# MyBuffer.net
KiCad netlist of a schematic drawn in EAGLE
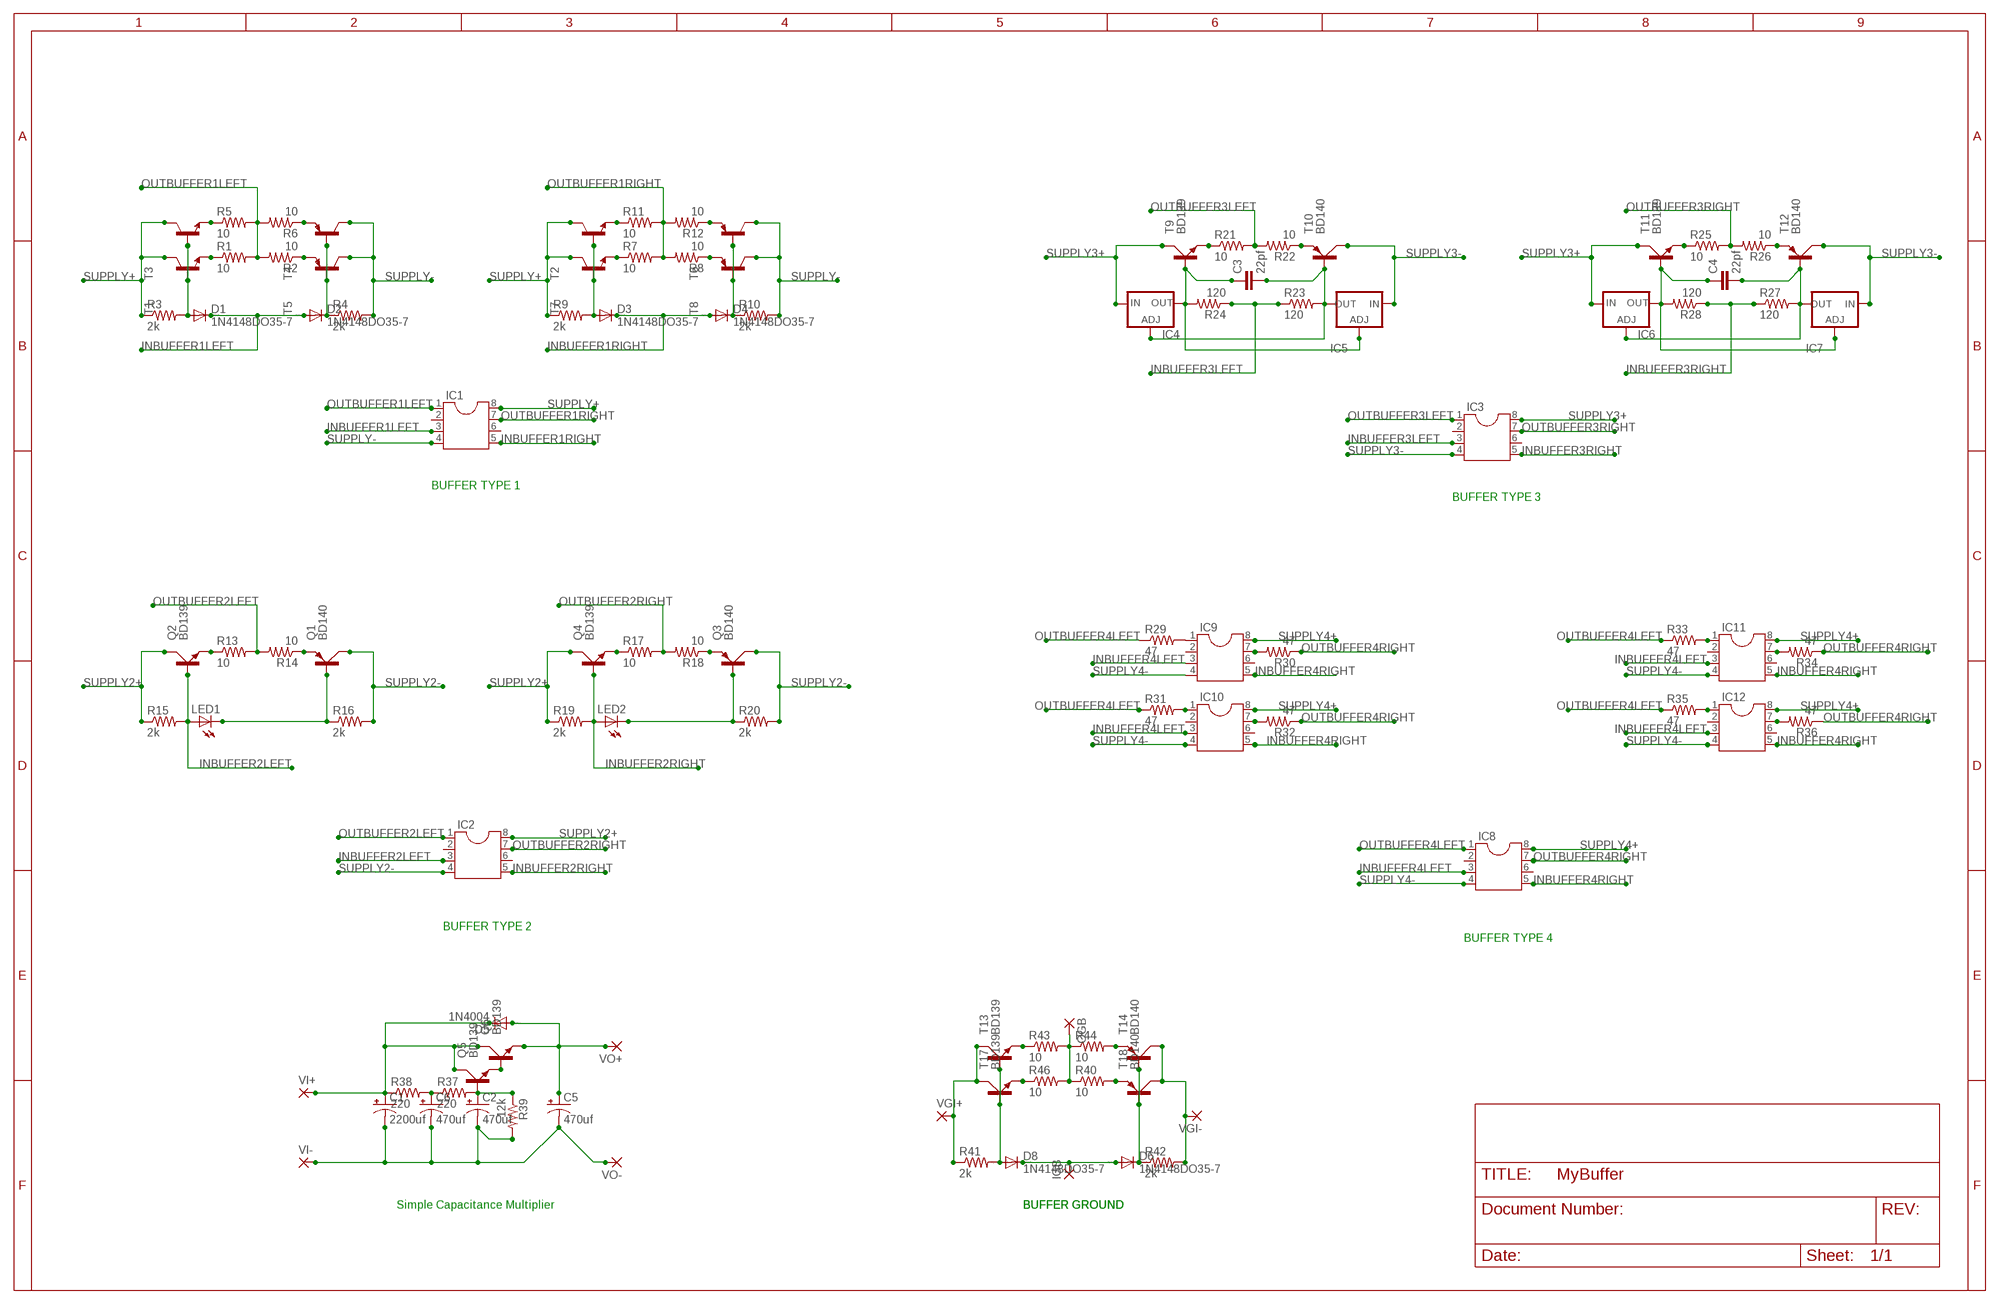
[diagram p0: schematic, sheet 1]

(export (version "E")
  (design (tool "Eeschema 10.0.6"))
  (components
    (comp (ref "C1")
      (value "2200uf")
      (footprint "eagle-import:E7,5-16")
      (libsource (lib "eagle-import") (part "CPOL-USE7.5-16"))
    )
    (comp (ref "C2")
      (value "470uf")
      (footprint "eagle-import:E7,5-16")
      (libsource (lib "eagle-import") (part "CPOL-USE7.5-16"))
    )
    (comp (ref "C3")
      (value "22pf")
      (footprint "eagle-import:C5B2.5")
      (libsource (lib "eagle-import") (part "C5/2.5"))
    )
    (comp (ref "C4")
      (value "22pf")
      (footprint "eagle-import:C5B2.5")
      (libsource (lib "eagle-import") (part "C5/2.5"))
    )
    (comp (ref "C5")
      (value "470uf")
      (footprint "eagle-import:E7,5-16")
      (libsource (lib "eagle-import") (part "CPOL-USE7.5-16"))
    )
    (comp (ref "C6")
      (value "470uf")
      (footprint "eagle-import:E7,5-16")
      (libsource (lib "eagle-import") (part "CPOL-USE7.5-16"))
    )
    (comp (ref "D1")
      (value "1N4148DO35-7")
      (footprint "eagle-import:DO35-7")
      (libsource (lib "eagle-import") (part "1N4148DO35-7"))
    )
    (comp (ref "D2")
      (value "1N4148DO35-7")
      (footprint "eagle-import:DO35-7")
      (libsource (lib "eagle-import") (part "1N4148DO35-7"))
    )
    (comp (ref "D3")
      (value "1N4148DO35-7")
      (footprint "eagle-import:DO35-7")
      (libsource (lib "eagle-import") (part "1N4148DO35-7"))
    )
    (comp (ref "D4")
      (value "1N4148DO35-7")
      (footprint "eagle-import:DO35-7")
      (libsource (lib "eagle-import") (part "1N4148DO35-7"))
    )
    (comp (ref "D5")
      (value "1N4004")
      (footprint "eagle-import:DO41-10")
      (libsource (lib "eagle-import") (part "1N4004"))
    )
    (comp (ref "D6")
      (value "1N4148DO35-7")
      (footprint "eagle-import:DO35-7")
      (libsource (lib "eagle-import") (part "1N4148DO35-7"))
    )
    (comp (ref "D8")
      (value "1N4148DO35-7")
      (footprint "eagle-import:DO35-7")
      (libsource (lib "eagle-import") (part "1N4148DO35-7"))
    )
    (comp (ref "IC1")
      (value "DIL8")
      (footprint "eagle-import:DIL08")
      (libsource (lib "eagle-import") (part "DIL8"))
    )
    (comp (ref "IC2")
      (value "DIL8")
      (footprint "eagle-import:DIL08")
      (libsource (lib "eagle-import") (part "DIL8"))
    )
    (comp (ref "IC3")
      (value "DIL8")
      (footprint "eagle-import:DIL08")
      (libsource (lib "eagle-import") (part "DIL8"))
    )
    (comp (ref "IC4")
      (value "LM317TS")
      (footprint "eagle-import:317TS")
      (libsource (lib "eagle-import") (part "LM317TS"))
    )
    (comp (ref "IC5")
      (value "LM337TS")
      (footprint "eagle-import:337TS")
      (libsource (lib "eagle-import") (part "LM337TS"))
    )
    (comp (ref "IC6")
      (value "LM317TS")
      (footprint "eagle-import:317TS")
      (libsource (lib "eagle-import") (part "LM317TS"))
    )
    (comp (ref "IC7")
      (value "LM337TS")
      (footprint "eagle-import:337TS")
      (libsource (lib "eagle-import") (part "LM337TS"))
    )
    (comp (ref "IC8")
      (value "DIL8")
      (footprint "eagle-import:DIL08")
      (libsource (lib "eagle-import") (part "DIL8"))
    )
    (comp (ref "IC9")
      (value "DIL8")
      (footprint "eagle-import:DIL08")
      (libsource (lib "eagle-import") (part "DIL8"))
    )
    (comp (ref "IC10")
      (value "DIL8")
      (footprint "eagle-import:DIL08")
      (libsource (lib "eagle-import") (part "DIL8"))
    )
    (comp (ref "IC11")
      (value "DIL8")
      (footprint "eagle-import:DIL08")
      (libsource (lib "eagle-import") (part "DIL8"))
    )
    (comp (ref "IC12")
      (value "DIL8")
      (footprint "eagle-import:DIL08")
      (libsource (lib "eagle-import") (part "DIL8"))
    )
    (comp (ref "IGB")
      (value "2,54/0,8")
      (footprint "eagle-import:2,54_0,8")
      (libsource (lib "eagle-import") (part "2,54/0,8"))
    )
    (comp (ref "LED1")
      (value "LED3MM")
      (footprint "eagle-import:LED3MM")
      (libsource (lib "eagle-import") (part "LED3MM"))
    )
    (comp (ref "LED2")
      (value "LED3MM")
      (footprint "eagle-import:LED3MM")
      (libsource (lib "eagle-import") (part "LED3MM"))
    )
    (comp (ref "OGB")
      (value "2,54/0,8")
      (footprint "eagle-import:2,54_0,8")
      (libsource (lib "eagle-import") (part "2,54/0,8"))
    )
    (comp (ref "Q1")
      (value "BD140")
      (footprint "eagle-import:TO126AV")
      (libsource (lib "eagle-import") (part "BD140"))
    )
    (comp (ref "Q2")
      (value "BD139")
      (footprint "eagle-import:TO126AV")
      (libsource (lib "eagle-import") (part "BD139"))
    )
    (comp (ref "Q3")
      (value "BD140")
      (footprint "eagle-import:TO126AV")
      (libsource (lib "eagle-import") (part "BD140"))
    )
    (comp (ref "Q4")
      (value "BD139")
      (footprint "eagle-import:TO126AV")
      (libsource (lib "eagle-import") (part "BD139"))
    )
    (comp (ref "Q5")
      (value "BD139")
      (footprint "eagle-import:TO126AV")
      (libsource (lib "eagle-import") (part "BD139"))
    )
    (comp (ref "Q6")
      (value "BD139")
      (footprint "eagle-import:TO126AV")
      (libsource (lib "eagle-import") (part "BD139"))
    )
    (comp (ref "R1")
      (value "10")
      (footprint "eagle-import:0207_10")
      (libsource (lib "eagle-import") (part "R-US_0207/10"))
    )
    (comp (ref "R2")
      (value "10")
      (footprint "eagle-import:0207_10")
      (libsource (lib "eagle-import") (part "R-US_0207/10"))
    )
    (comp (ref "R3")
      (value "2k")
      (footprint "eagle-import:0207_10")
      (libsource (lib "eagle-import") (part "R-US_0207/10"))
    )
    (comp (ref "R4")
      (value "2k")
      (footprint "eagle-import:0207_10")
      (libsource (lib "eagle-import") (part "R-US_0207/10"))
    )
    (comp (ref "R5")
      (value "10")
      (footprint "eagle-import:0207_2V")
      (libsource (lib "eagle-import") (part "R-US_0207/2V"))
    )
    (comp (ref "R6")
      (value "10")
      (footprint "eagle-import:0207_2V")
      (libsource (lib "eagle-import") (part "R-US_0207/2V"))
    )
    (comp (ref "R7")
      (value "10")
      (footprint "eagle-import:0207_10")
      (libsource (lib "eagle-import") (part "R-US_0207/10"))
    )
    (comp (ref "R8")
      (value "10")
      (footprint "eagle-import:0207_10")
      (libsource (lib "eagle-import") (part "R-US_0207/10"))
    )
    (comp (ref "R9")
      (value "2k")
      (footprint "eagle-import:0207_10")
      (libsource (lib "eagle-import") (part "R-US_0207/10"))
    )
    (comp (ref "R10")
      (value "2k")
      (footprint "eagle-import:0207_10")
      (libsource (lib "eagle-import") (part "R-US_0207/10"))
    )
    (comp (ref "R11")
      (value "10")
      (footprint "eagle-import:0207_2V")
      (libsource (lib "eagle-import") (part "R-US_0207/2V"))
    )
    (comp (ref "R12")
      (value "10")
      (footprint "eagle-import:0207_2V")
      (libsource (lib "eagle-import") (part "R-US_0207/2V"))
    )
    (comp (ref "R13")
      (value "10")
      (footprint "eagle-import:0207_10")
      (libsource (lib "eagle-import") (part "R-US_0207/10"))
    )
    (comp (ref "R14")
      (value "10")
      (footprint "eagle-import:0207_10")
      (libsource (lib "eagle-import") (part "R-US_0207/10"))
    )
    (comp (ref "R15")
      (value "2k")
      (footprint "eagle-import:0207_10")
      (libsource (lib "eagle-import") (part "R-US_0207/10"))
    )
    (comp (ref "R16")
      (value "2k")
      (footprint "eagle-import:0207_10")
      (libsource (lib "eagle-import") (part "R-US_0207/10"))
    )
    (comp (ref "R17")
      (value "10")
      (footprint "eagle-import:0207_10")
      (libsource (lib "eagle-import") (part "R-US_0207/10"))
    )
    (comp (ref "R18")
      (value "10")
      (footprint "eagle-import:0207_10")
      (libsource (lib "eagle-import") (part "R-US_0207/10"))
    )
    (comp (ref "R19")
      (value "2k")
      (footprint "eagle-import:0207_10")
      (libsource (lib "eagle-import") (part "R-US_0207/10"))
    )
    (comp (ref "R20")
      (value "2k")
      (footprint "eagle-import:0207_10")
      (libsource (lib "eagle-import") (part "R-US_0207/10"))
    )
    (comp (ref "R21")
      (value "10")
      (footprint "eagle-import:0207_10")
      (libsource (lib "eagle-import") (part "R-US_0207/10"))
    )
    (comp (ref "R22")
      (value "10")
      (footprint "eagle-import:0207_10")
      (libsource (lib "eagle-import") (part "R-US_0207/10"))
    )
    (comp (ref "R23")
      (value "120")
      (footprint "eagle-import:0207_10")
      (libsource (lib "eagle-import") (part "R-US_0207/10"))
    )
    (comp (ref "R24")
      (value "120")
      (footprint "eagle-import:0207_10")
      (libsource (lib "eagle-import") (part "R-US_0207/10"))
    )
    (comp (ref "R25")
      (value "10")
      (footprint "eagle-import:0207_10")
      (libsource (lib "eagle-import") (part "R-US_0207/10"))
    )
    (comp (ref "R26")
      (value "10")
      (footprint "eagle-import:0207_10")
      (libsource (lib "eagle-import") (part "R-US_0207/10"))
    )
    (comp (ref "R27")
      (value "120")
      (footprint "eagle-import:0207_10")
      (libsource (lib "eagle-import") (part "R-US_0207/10"))
    )
    (comp (ref "R28")
      (value "120")
      (footprint "eagle-import:0207_10")
      (libsource (lib "eagle-import") (part "R-US_0207/10"))
    )
    (comp (ref "R29")
      (value "47")
      (footprint "eagle-import:0207_10")
      (libsource (lib "eagle-import") (part "R-US_0207/10"))
    )
    (comp (ref "R30")
      (value "47")
      (footprint "eagle-import:0207_10")
      (libsource (lib "eagle-import") (part "R-US_0207/10"))
    )
    (comp (ref "R31")
      (value "47")
      (footprint "eagle-import:0207_10")
      (libsource (lib "eagle-import") (part "R-US_0207/10"))
    )
    (comp (ref "R32")
      (value "47")
      (footprint "eagle-import:0207_10")
      (libsource (lib "eagle-import") (part "R-US_0207/10"))
    )
    (comp (ref "R33")
      (value "47")
      (footprint "eagle-import:0207_10")
      (libsource (lib "eagle-import") (part "R-US_0207/10"))
    )
    (comp (ref "R34")
      (value "47")
      (footprint "eagle-import:0207_10")
      (libsource (lib "eagle-import") (part "R-US_0207/10"))
    )
    (comp (ref "R35")
      (value "47")
      (footprint "eagle-import:0207_10")
      (libsource (lib "eagle-import") (part "R-US_0207/10"))
    )
    (comp (ref "R36")
      (value "47")
      (footprint "eagle-import:0207_10")
      (libsource (lib "eagle-import") (part "R-US_0207/10"))
    )
    (comp (ref "R37")
      (value "220")
      (footprint "eagle-import:0207_10")
      (libsource (lib "eagle-import") (part "R-US_0207/10"))
    )
    (comp (ref "R38")
      (value "220")
      (footprint "eagle-import:0207_10")
      (libsource (lib "eagle-import") (part "R-US_0207/10"))
    )
    (comp (ref "R39")
      (value "12k")
      (footprint "eagle-import:0207_10")
      (libsource (lib "eagle-import") (part "R-US_0207/10"))
    )
    (comp (ref "R40")
      (value "10")
      (footprint "eagle-import:0207_10")
      (libsource (lib "eagle-import") (part "R-US_0207/10"))
    )
    (comp (ref "R41")
      (value "2k")
      (footprint "eagle-import:0207_10")
      (libsource (lib "eagle-import") (part "R-US_0207/10"))
    )
    (comp (ref "R42")
      (value "2k")
      (footprint "eagle-import:0207_10")
      (libsource (lib "eagle-import") (part "R-US_0207/10"))
    )
    (comp (ref "R43")
      (value "10")
      (footprint "eagle-import:0207_10")
      (libsource (lib "eagle-import") (part "R-US_0207/10"))
    )
    (comp (ref "R44")
      (value "10")
      (footprint "eagle-import:0207_10")
      (libsource (lib "eagle-import") (part "R-US_0207/10"))
    )
    (comp (ref "R46")
      (value "10")
      (footprint "eagle-import:0207_10")
      (libsource (lib "eagle-import") (part "R-US_0207/10"))
    )
    (comp (ref "T1")
      (value "29-NPN-TO92-EBC")
      (footprint "eagle-import:TO92-EBC")
      (libsource (lib "eagle-import") (part "-NPN-TO92-EBC29"))
    )
    (comp (ref "T2")
      (value "29-NPN-TO92-EBC")
      (footprint "eagle-import:TO92-EBC")
      (libsource (lib "eagle-import") (part "-NPN-TO92-EBC29"))
    )
    (comp (ref "T3")
      (value "29-NPN-TO92-EBC")
      (footprint "eagle-import:TO92-EBC")
      (libsource (lib "eagle-import") (part "-NPN-TO92-EBC29"))
    )
    (comp (ref "T4")
      (value "2N5401-PNP-TO92-EBC")
      (footprint "eagle-import:TO92-EBC")
      (libsource (lib "eagle-import") (part "-PNP-TO92-EBC2N5401"))
    )
    (comp (ref "T5")
      (value "2N5401-PNP-TO92-EBC")
      (footprint "eagle-import:TO92-EBC")
      (libsource (lib "eagle-import") (part "-PNP-TO92-EBC2N5401"))
    )
    (comp (ref "T6")
      (value "2N5401-PNP-TO92-EBC")
      (footprint "eagle-import:TO92-EBC")
      (libsource (lib "eagle-import") (part "-PNP-TO92-EBC2N5401"))
    )
    (comp (ref "T7")
      (value "29-NPN-TO92-EBC")
      (footprint "eagle-import:TO92-EBC")
      (libsource (lib "eagle-import") (part "-NPN-TO92-EBC29"))
    )
    (comp (ref "T8")
      (value "2N5401-PNP-TO92-EBC")
      (footprint "eagle-import:TO92-EBC")
      (libsource (lib "eagle-import") (part "-PNP-TO92-EBC2N5401"))
    )
    (comp (ref "T9")
      (value "BD139")
      (footprint "eagle-import:TO126AV")
      (libsource (lib "eagle-import") (part "BD139"))
    )
    (comp (ref "T10")
      (value "BD140")
      (footprint "eagle-import:TO126AV")
      (libsource (lib "eagle-import") (part "BD140"))
    )
    (comp (ref "T11")
      (value "BD139")
      (footprint "eagle-import:TO126AV")
      (libsource (lib "eagle-import") (part "BD139"))
    )
    (comp (ref "T12")
      (value "BD140")
      (footprint "eagle-import:TO126AV")
      (libsource (lib "eagle-import") (part "BD140"))
    )
    (comp (ref "T13")
      (value "BD139")
      (footprint "eagle-import:TO126AV")
      (libsource (lib "eagle-import") (part "BD139"))
    )
    (comp (ref "T14")
      (value "BD140")
      (footprint "eagle-import:TO126AV")
      (libsource (lib "eagle-import") (part "BD140"))
    )
    (comp (ref "T17")
      (value "BD139")
      (footprint "eagle-import:TO126AV")
      (libsource (lib "eagle-import") (part "BD139"))
    )
    (comp (ref "T18")
      (value "BD140")
      (footprint "eagle-import:TO126AV")
      (libsource (lib "eagle-import") (part "BD140"))
    )
    (comp (ref "VGI+")
      (value "2,54/0,8")
      (footprint "eagle-import:2,54_0,8")
      (libsource (lib "eagle-import") (part "2,54/0,8"))
    )
    (comp (ref "VGI-")
      (value "2,54/0,8")
      (footprint "eagle-import:2,54_0,8")
      (libsource (lib "eagle-import") (part "2,54/0,8"))
    )
    (comp (ref "VI+")
      (value "2,54/0,8")
      (footprint "eagle-import:2,54_0,8")
      (libsource (lib "eagle-import") (part "2,54/0,8"))
    )
    (comp (ref "VI-")
      (value "2,54/0,8")
      (footprint "eagle-import:2,54_0,8")
      (libsource (lib "eagle-import") (part "2,54/0,8"))
    )
    (comp (ref "VO+")
      (value "2,54/0,8")
      (footprint "eagle-import:2,54_0,8")
      (libsource (lib "eagle-import") (part "2,54/0,8"))
    )
    (comp (ref "VO-")
      (value "2,54/0,8")
      (footprint "eagle-import:2,54_0,8")
      (libsource (lib "eagle-import") (part "2,54/0,8"))
    )
  )
  (nets
    (net (code "1") (name "/INBUFFER1LEFT") (class "Default")
      (node (ref "D1") (pin "C") (pinfunction "C_C") (pintype "passive"))
      (node (ref "D2") (pin "A") (pinfunction "A_A") (pintype "passive"))
      (node (ref "IC1") (pin "3") (pinfunction "3_3") (pintype "passive"))
    )
    (net (code "2") (name "/INBUFFER1RIGHT") (class "Default")
      (node (ref "D3") (pin "C") (pinfunction "C_C") (pintype "passive"))
      (node (ref "D4") (pin "A") (pinfunction "A_A") (pintype "passive"))
      (node (ref "IC1") (pin "5") (pinfunction "5_5") (pintype "passive"))
    )
    (net (code "3") (name "/INBUFFER2LEFT") (class "Default")
      (node (ref "IC2") (pin "3") (pinfunction "3_3") (pintype "passive"))
      (node (ref "LED1") (pin "A") (pinfunction "A_A") (pintype "passive"))
      (node (ref "Q2") (pin "B") (pinfunction "B_B") (pintype "passive"))
      (node (ref "R15") (pin "2") (pinfunction "2_2") (pintype "passive"))
    )
    (net (code "4") (name "/INBUFFER2RIGHT") (class "Default")
      (node (ref "IC2") (pin "5") (pinfunction "5_5") (pintype "passive"))
      (node (ref "LED2") (pin "A") (pinfunction "A_A") (pintype "passive"))
      (node (ref "Q4") (pin "B") (pinfunction "B_B") (pintype "passive"))
      (node (ref "R19") (pin "2") (pinfunction "2_2") (pintype "passive"))
    )
    (net (code "5") (name "/INBUFFER3LEFT") (class "Default")
      (node (ref "IC3") (pin "3") (pinfunction "3_3") (pintype "passive"))
      (node (ref "R23") (pin "1") (pinfunction "1_1") (pintype "passive"))
      (node (ref "R24") (pin "1") (pinfunction "1_1") (pintype "passive"))
    )
    (net (code "6") (name "/INBUFFER3RIGHT") (class "Default")
      (node (ref "IC3") (pin "5") (pinfunction "5_5") (pintype "passive"))
      (node (ref "R27") (pin "1") (pinfunction "1_1") (pintype "passive"))
      (node (ref "R28") (pin "1") (pinfunction "1_1") (pintype "passive"))
    )
    (net (code "7") (name "/INBUFFER4LEFT") (class "Default")
      (node (ref "IC10") (pin "3") (pinfunction "3_3") (pintype "passive"))
      (node (ref "IC11") (pin "3") (pinfunction "3_3") (pintype "passive"))
      (node (ref "IC12") (pin "3") (pinfunction "3_3") (pintype "passive"))
      (node (ref "IC8") (pin "3") (pinfunction "3_3") (pintype "passive"))
      (node (ref "IC9") (pin "3") (pinfunction "3_3") (pintype "passive"))
    )
    (net (code "8") (name "/INBUFFER4RIGHT") (class "Default")
      (node (ref "IC10") (pin "5") (pinfunction "5_5") (pintype "passive"))
      (node (ref "IC11") (pin "5") (pinfunction "5_5") (pintype "passive"))
      (node (ref "IC12") (pin "5") (pinfunction "5_5") (pintype "passive"))
      (node (ref "IC8") (pin "5") (pinfunction "5_5") (pintype "passive"))
      (node (ref "IC9") (pin "5") (pinfunction "5_5") (pintype "passive"))
    )
    (net (code "9") (name "/OUTBUFFER1LEFT") (class "Default")
      (node (ref "IC1") (pin "1") (pinfunction "1_1") (pintype "passive"))
      (node (ref "R1") (pin "2") (pinfunction "2_2") (pintype "passive"))
      (node (ref "R2") (pin "2") (pinfunction "2_2") (pintype "passive"))
      (node (ref "R5") (pin "2") (pinfunction "2_2") (pintype "passive"))
      (node (ref "R6") (pin "2") (pinfunction "2_2") (pintype "passive"))
    )
    (net (code "10") (name "/OUTBUFFER1RIGHT") (class "Default")
      (node (ref "IC1") (pin "7") (pinfunction "7_7") (pintype "passive"))
      (node (ref "R11") (pin "2") (pinfunction "2_2") (pintype "passive"))
      (node (ref "R12") (pin "2") (pinfunction "2_2") (pintype "passive"))
      (node (ref "R7") (pin "2") (pinfunction "2_2") (pintype "passive"))
      (node (ref "R8") (pin "2") (pinfunction "2_2") (pintype "passive"))
    )
    (net (code "11") (name "/OUTBUFFER2LEFT") (class "Default")
      (node (ref "IC2") (pin "1") (pinfunction "1_1") (pintype "passive"))
      (node (ref "R13") (pin "2") (pinfunction "2_2") (pintype "passive"))
      (node (ref "R14") (pin "2") (pinfunction "2_2") (pintype "passive"))
    )
    (net (code "12") (name "/OUTBUFFER2RIGHT") (class "Default")
      (node (ref "IC2") (pin "7") (pinfunction "7_7") (pintype "passive"))
      (node (ref "R17") (pin "2") (pinfunction "2_2") (pintype "passive"))
      (node (ref "R18") (pin "2") (pinfunction "2_2") (pintype "passive"))
    )
    (net (code "13") (name "/OUTBUFFER3LEFT") (class "Default")
      (node (ref "IC3") (pin "1") (pinfunction "1_1") (pintype "passive"))
      (node (ref "R21") (pin "2") (pinfunction "2_2") (pintype "passive"))
      (node (ref "R22") (pin "2") (pinfunction "2_2") (pintype "passive"))
    )
    (net (code "14") (name "/OUTBUFFER3RIGHT") (class "Default")
      (node (ref "IC3") (pin "7") (pinfunction "7_7") (pintype "passive"))
      (node (ref "R25") (pin "2") (pinfunction "2_2") (pintype "passive"))
      (node (ref "R26") (pin "2") (pinfunction "2_2") (pintype "passive"))
    )
    (net (code "15") (name "/OUTBUFFER4LEFT") (class "Default")
      (node (ref "IC8") (pin "1") (pinfunction "1_1") (pintype "passive"))
      (node (ref "R29") (pin "1") (pinfunction "1_1") (pintype "passive"))
      (node (ref "R31") (pin "1") (pinfunction "1_1") (pintype "passive"))
      (node (ref "R33") (pin "1") (pinfunction "1_1") (pintype "passive"))
      (node (ref "R35") (pin "1") (pinfunction "1_1") (pintype "passive"))
    )
    (net (code "16") (name "/OUTBUFFER4RIGHT") (class "Default")
      (node (ref "IC8") (pin "7") (pinfunction "7_7") (pintype "passive"))
      (node (ref "R30") (pin "1") (pinfunction "1_1") (pintype "passive"))
      (node (ref "R32") (pin "1") (pinfunction "1_1") (pintype "passive"))
      (node (ref "R34") (pin "1") (pinfunction "1_1") (pintype "passive"))
      (node (ref "R36") (pin "1") (pinfunction "1_1") (pintype "passive"))
    )
    (net (code "17") (name "/SUPPLY+") (class "Default")
      (node (ref "IC1") (pin "8") (pinfunction "8_8") (pintype "passive"))
      (node (ref "R3") (pin "1") (pinfunction "1_1") (pintype "passive"))
      (node (ref "R9") (pin "1") (pinfunction "1_1") (pintype "passive"))
      (node (ref "T1") (pin "C") (pinfunction "C_C") (pintype "passive"))
      (node (ref "T2") (pin "C") (pinfunction "C_C") (pintype "passive"))
      (node (ref "T3") (pin "C") (pinfunction "C_C") (pintype "passive"))
      (node (ref "T7") (pin "C") (pinfunction "C_C") (pintype "passive"))
    )
    (net (code "18") (name "/SUPPLY-") (class "Default")
      (node (ref "IC1") (pin "4") (pinfunction "4_4") (pintype "passive"))
      (node (ref "R10") (pin "2") (pinfunction "2_2") (pintype "passive"))
      (node (ref "R4") (pin "2") (pinfunction "2_2") (pintype "passive"))
      (node (ref "T4") (pin "C") (pinfunction "C_C") (pintype "passive"))
      (node (ref "T5") (pin "C") (pinfunction "C_C") (pintype "passive"))
      (node (ref "T6") (pin "C") (pinfunction "C_C") (pintype "passive"))
      (node (ref "T8") (pin "C") (pinfunction "C_C") (pintype "passive"))
    )
    (net (code "19") (name "/SUPPLY2+") (class "Default")
      (node (ref "IC2") (pin "8") (pinfunction "8_8") (pintype "passive"))
      (node (ref "Q2") (pin "C") (pinfunction "C_C") (pintype "passive"))
      (node (ref "Q4") (pin "C") (pinfunction "C_C") (pintype "passive"))
      (node (ref "R15") (pin "1") (pinfunction "1_1") (pintype "passive"))
      (node (ref "R19") (pin "1") (pinfunction "1_1") (pintype "passive"))
    )
    (net (code "20") (name "/SUPPLY2-") (class "Default")
      (node (ref "IC2") (pin "4") (pinfunction "4_4") (pintype "passive"))
      (node (ref "Q1") (pin "C") (pinfunction "C_C") (pintype "passive"))
      (node (ref "Q3") (pin "C") (pinfunction "C_C") (pintype "passive"))
      (node (ref "R16") (pin "2") (pinfunction "2_2") (pintype "passive"))
      (node (ref "R20") (pin "2") (pinfunction "2_2") (pintype "passive"))
    )
    (net (code "21") (name "/SUPPLY3+") (class "Default")
      (node (ref "IC3") (pin "8") (pinfunction "8_8") (pintype "passive"))
      (node (ref "IC4") (pin "3") (pinfunction "IN_3") (pintype "input"))
      (node (ref "IC6") (pin "3") (pinfunction "IN_3") (pintype "input"))
      (node (ref "T11") (pin "C") (pinfunction "C_C") (pintype "passive"))
      (node (ref "T9") (pin "C") (pinfunction "C_C") (pintype "passive"))
    )
    (net (code "22") (name "/SUPPLY3-") (class "Default")
      (node (ref "IC3") (pin "4") (pinfunction "4_4") (pintype "passive"))
      (node (ref "IC5") (pin "2") (pinfunction "IN_2") (pintype "input"))
      (node (ref "IC7") (pin "2") (pinfunction "IN_2") (pintype "input"))
      (node (ref "T10") (pin "C") (pinfunction "C_C") (pintype "passive"))
      (node (ref "T12") (pin "C") (pinfunction "C_C") (pintype "passive"))
    )
    (net (code "23") (name "/SUPPLY4+") (class "Default")
      (node (ref "IC10") (pin "8") (pinfunction "8_8") (pintype "passive"))
      (node (ref "IC11") (pin "8") (pinfunction "8_8") (pintype "passive"))
      (node (ref "IC12") (pin "8") (pinfunction "8_8") (pintype "passive"))
      (node (ref "IC8") (pin "8") (pinfunction "8_8") (pintype "passive"))
      (node (ref "IC9") (pin "8") (pinfunction "8_8") (pintype "passive"))
    )
    (net (code "24") (name "/SUPPLY4-") (class "Default")
      (node (ref "IC10") (pin "4") (pinfunction "4_4") (pintype "passive"))
      (node (ref "IC11") (pin "4") (pinfunction "4_4") (pintype "passive"))
      (node (ref "IC12") (pin "4") (pinfunction "4_4") (pintype "passive"))
      (node (ref "IC8") (pin "4") (pinfunction "4_4") (pintype "passive"))
      (node (ref "IC9") (pin "4") (pinfunction "4_4") (pintype "passive"))
    )
    (net (code "25") (name "Net-(C2-Pad+)") (class "Default")
      (node (ref "C2") (pin "+") (pinfunction "+_+") (pintype "passive"))
      (node (ref "Q5") (pin "B") (pinfunction "B_B") (pintype "passive"))
      (node (ref "R37") (pin "2") (pinfunction "2_2") (pintype "passive"))
      (node (ref "R39") (pin "1") (pinfunction "1_1") (pintype "passive"))
    )
    (net (code "26") (name "Net-(C6-Pad+)") (class "Default")
      (node (ref "C6") (pin "+") (pinfunction "+_+") (pintype "passive"))
      (node (ref "R37") (pin "1") (pinfunction "1_1") (pintype "passive"))
      (node (ref "R38") (pin "2") (pinfunction "2_2") (pintype "passive"))
    )
    (net (code "27") (name "Net-(D1-PadA)") (class "Default")
      (node (ref "D1") (pin "A") (pinfunction "A_A") (pintype "passive"))
      (node (ref "R3") (pin "2") (pinfunction "2_2") (pintype "passive"))
      (node (ref "T1") (pin "B") (pinfunction "B_B") (pintype "passive"))
      (node (ref "T3") (pin "B") (pinfunction "B_B") (pintype "passive"))
    )
    (net (code "28") (name "Net-(D2-PadC)") (class "Default")
      (node (ref "D2") (pin "C") (pinfunction "C_C") (pintype "passive"))
      (node (ref "R4") (pin "1") (pinfunction "1_1") (pintype "passive"))
      (node (ref "T4") (pin "B") (pinfunction "B_B") (pintype "passive"))
      (node (ref "T5") (pin "B") (pinfunction "B_B") (pintype "passive"))
    )
    (net (code "29") (name "Net-(D3-PadA)") (class "Default")
      (node (ref "D3") (pin "A") (pinfunction "A_A") (pintype "passive"))
      (node (ref "R9") (pin "2") (pinfunction "2_2") (pintype "passive"))
      (node (ref "T2") (pin "B") (pinfunction "B_B") (pintype "passive"))
      (node (ref "T7") (pin "B") (pinfunction "B_B") (pintype "passive"))
    )
    (net (code "30") (name "Net-(D4-PadC)") (class "Default")
      (node (ref "D4") (pin "C") (pinfunction "C_C") (pintype "passive"))
      (node (ref "R10") (pin "1") (pinfunction "1_1") (pintype "passive"))
      (node (ref "T6") (pin "B") (pinfunction "B_B") (pintype "passive"))
      (node (ref "T8") (pin "B") (pinfunction "B_B") (pintype "passive"))
    )
    (net (code "31") (name "Net-(D6-PadC)") (class "Default")
      (node (ref "D6") (pin "C") (pinfunction "C_C") (pintype "passive"))
      (node (ref "R42") (pin "1") (pinfunction "1_1") (pintype "passive"))
      (node (ref "T14") (pin "B") (pinfunction "B_B") (pintype "passive"))
      (node (ref "T18") (pin "B") (pinfunction "B_B") (pintype "passive"))
    )
    (net (code "32") (name "Net-(D8-PadA)") (class "Default")
      (node (ref "D8") (pin "A") (pinfunction "A_A") (pintype "passive"))
      (node (ref "R41") (pin "2") (pinfunction "2_2") (pintype "passive"))
      (node (ref "T13") (pin "B") (pinfunction "B_B") (pintype "passive"))
      (node (ref "T17") (pin "B") (pinfunction "B_B") (pintype "passive"))
    )
    (net (code "33") (name "Net-(IC4-ADJ)") (class "Default")
      (node (ref "C3") (pin "2") (pinfunction "2_2") (pintype "passive"))
      (node (ref "IC4") (pin "1") (pinfunction "ADJ_1") (pintype "input"))
      (node (ref "IC5") (pin "3") (pinfunction "OUT_3") (pintype "passive"))
      (node (ref "R23") (pin "2") (pinfunction "2_2") (pintype "passive"))
      (node (ref "T10") (pin "B") (pinfunction "B_B") (pintype "passive"))
    )
    (net (code "34") (name "Net-(IC4-OUT)") (class "Default")
      (node (ref "C3") (pin "1") (pinfunction "1_1") (pintype "passive"))
      (node (ref "IC4") (pin "2") (pinfunction "OUT_2") (pintype "passive"))
      (node (ref "IC5") (pin "1") (pinfunction "ADJ_1") (pintype "input"))
      (node (ref "R24") (pin "2") (pinfunction "2_2") (pintype "passive"))
      (node (ref "T9") (pin "B") (pinfunction "B_B") (pintype "passive"))
    )
    (net (code "35") (name "Net-(IC6-ADJ)") (class "Default")
      (node (ref "C4") (pin "2") (pinfunction "2_2") (pintype "passive"))
      (node (ref "IC6") (pin "1") (pinfunction "ADJ_1") (pintype "input"))
      (node (ref "IC7") (pin "3") (pinfunction "OUT_3") (pintype "passive"))
      (node (ref "R27") (pin "2") (pinfunction "2_2") (pintype "passive"))
      (node (ref "T12") (pin "B") (pinfunction "B_B") (pintype "passive"))
    )
    (net (code "36") (name "Net-(IC6-OUT)") (class "Default")
      (node (ref "C4") (pin "1") (pinfunction "1_1") (pintype "passive"))
      (node (ref "IC6") (pin "2") (pinfunction "OUT_2") (pintype "passive"))
      (node (ref "IC7") (pin "1") (pinfunction "ADJ_1") (pintype "input"))
      (node (ref "R28") (pin "2") (pinfunction "2_2") (pintype "passive"))
      (node (ref "T11") (pin "B") (pinfunction "B_B") (pintype "passive"))
    )
    (net (code "37") (name "Net-(IC9-Pad1)") (class "Default")
      (node (ref "IC9") (pin "1") (pinfunction "1_1") (pintype "passive"))
      (node (ref "R29") (pin "2") (pinfunction "2_2") (pintype "passive"))
    )
    (net (code "38") (name "Net-(IC9-Pad7)") (class "Default")
      (node (ref "IC9") (pin "7") (pinfunction "7_7") (pintype "passive"))
      (node (ref "R30") (pin "2") (pinfunction "2_2") (pintype "passive"))
    )
    (net (code "39") (name "Net-(IC10-Pad1)") (class "Default")
      (node (ref "IC10") (pin "1") (pinfunction "1_1") (pintype "passive"))
      (node (ref "R31") (pin "2") (pinfunction "2_2") (pintype "passive"))
    )
    (net (code "40") (name "Net-(IC10-Pad7)") (class "Default")
      (node (ref "IC10") (pin "7") (pinfunction "7_7") (pintype "passive"))
      (node (ref "R32") (pin "2") (pinfunction "2_2") (pintype "passive"))
    )
    (net (code "41") (name "Net-(IC11-Pad1)") (class "Default")
      (node (ref "IC11") (pin "1") (pinfunction "1_1") (pintype "passive"))
      (node (ref "R33") (pin "2") (pinfunction "2_2") (pintype "passive"))
    )
    (net (code "42") (name "Net-(IC11-Pad7)") (class "Default")
      (node (ref "IC11") (pin "7") (pinfunction "7_7") (pintype "passive"))
      (node (ref "R34") (pin "2") (pinfunction "2_2") (pintype "passive"))
    )
    (net (code "43") (name "Net-(IC12-Pad1)") (class "Default")
      (node (ref "IC12") (pin "1") (pinfunction "1_1") (pintype "passive"))
      (node (ref "R35") (pin "2") (pinfunction "2_2") (pintype "passive"))
    )
    (net (code "44") (name "Net-(IC12-Pad7)") (class "Default")
      (node (ref "IC12") (pin "7") (pinfunction "7_7") (pintype "passive"))
      (node (ref "R36") (pin "2") (pinfunction "2_2") (pintype "passive"))
    )
    (net (code "45") (name "Net-(IGB-P)") (class "Default")
      (node (ref "D6") (pin "A") (pinfunction "A_A") (pintype "passive"))
      (node (ref "D8") (pin "C") (pinfunction "C_C") (pintype "passive"))
      (node (ref "IGB") (pin "1") (pinfunction "P_1") (pintype "passive"))
    )
    (net (code "46") (name "Net-(LED1-C)") (class "Default")
      (node (ref "LED1") (pin "K") (pinfunction "C_K") (pintype "passive"))
      (node (ref "Q1") (pin "B") (pinfunction "B_B") (pintype "passive"))
      (node (ref "R16") (pin "1") (pinfunction "1_1") (pintype "passive"))
    )
    (net (code "47") (name "Net-(LED2-C)") (class "Default")
      (node (ref "LED2") (pin "K") (pinfunction "C_K") (pintype "passive"))
      (node (ref "Q3") (pin "B") (pinfunction "B_B") (pintype "passive"))
      (node (ref "R20") (pin "1") (pinfunction "1_1") (pintype "passive"))
    )
    (net (code "48") (name "Net-(OGB-P)") (class "Default")
      (node (ref "OGB") (pin "1") (pinfunction "P_1") (pintype "passive"))
      (node (ref "R40") (pin "1") (pinfunction "1_1") (pintype "passive"))
      (node (ref "R43") (pin "2") (pinfunction "2_2") (pintype "passive"))
      (node (ref "R44") (pin "1") (pinfunction "1_1") (pintype "passive"))
      (node (ref "R46") (pin "2") (pinfunction "2_2") (pintype "passive"))
    )
    (net (code "49") (name "Net-(Q1-PadE)") (class "Default")
      (node (ref "Q1") (pin "E") (pinfunction "E_E") (pintype "passive"))
      (node (ref "R14") (pin "1") (pinfunction "1_1") (pintype "passive"))
    )
    (net (code "50") (name "Net-(Q2-PadE)") (class "Default")
      (node (ref "Q2") (pin "E") (pinfunction "E_E") (pintype "passive"))
      (node (ref "R13") (pin "1") (pinfunction "1_1") (pintype "passive"))
    )
    (net (code "51") (name "Net-(Q3-PadE)") (class "Default")
      (node (ref "Q3") (pin "E") (pinfunction "E_E") (pintype "passive"))
      (node (ref "R18") (pin "1") (pinfunction "1_1") (pintype "passive"))
    )
    (net (code "52") (name "Net-(Q4-PadE)") (class "Default")
      (node (ref "Q4") (pin "E") (pinfunction "E_E") (pintype "passive"))
      (node (ref "R17") (pin "1") (pinfunction "1_1") (pintype "passive"))
    )
    (net (code "53") (name "Net-(Q5-PadE)") (class "Default")
      (node (ref "Q5") (pin "E") (pinfunction "E_E") (pintype "passive"))
      (node (ref "Q6") (pin "B") (pinfunction "B_B") (pintype "passive"))
    )
    (net (code "54") (name "Net-(R1-Pad1)") (class "Default")
      (node (ref "R1") (pin "1") (pinfunction "1_1") (pintype "passive"))
      (node (ref "T1") (pin "E") (pinfunction "E_E") (pintype "passive"))
    )
    (net (code "55") (name "Net-(R2-Pad1)") (class "Default")
      (node (ref "R2") (pin "1") (pinfunction "1_1") (pintype "passive"))
      (node (ref "T5") (pin "E") (pinfunction "E_E") (pintype "passive"))
    )
    (net (code "56") (name "Net-(R5-Pad1)") (class "Default")
      (node (ref "R5") (pin "1") (pinfunction "1_1") (pintype "passive"))
      (node (ref "T3") (pin "E") (pinfunction "E_E") (pintype "passive"))
    )
    (net (code "57") (name "Net-(R6-Pad1)") (class "Default")
      (node (ref "R6") (pin "1") (pinfunction "1_1") (pintype "passive"))
      (node (ref "T4") (pin "E") (pinfunction "E_E") (pintype "passive"))
    )
    (net (code "58") (name "Net-(R7-Pad1)") (class "Default")
      (node (ref "R7") (pin "1") (pinfunction "1_1") (pintype "passive"))
      (node (ref "T7") (pin "E") (pinfunction "E_E") (pintype "passive"))
    )
    (net (code "59") (name "Net-(R8-Pad1)") (class "Default")
      (node (ref "R8") (pin "1") (pinfunction "1_1") (pintype "passive"))
      (node (ref "T8") (pin "E") (pinfunction "E_E") (pintype "passive"))
    )
    (net (code "60") (name "Net-(R11-Pad1)") (class "Default")
      (node (ref "R11") (pin "1") (pinfunction "1_1") (pintype "passive"))
      (node (ref "T2") (pin "E") (pinfunction "E_E") (pintype "passive"))
    )
    (net (code "61") (name "Net-(R12-Pad1)") (class "Default")
      (node (ref "R12") (pin "1") (pinfunction "1_1") (pintype "passive"))
      (node (ref "T6") (pin "E") (pinfunction "E_E") (pintype "passive"))
    )
    (net (code "62") (name "Net-(R21-Pad1)") (class "Default")
      (node (ref "R21") (pin "1") (pinfunction "1_1") (pintype "passive"))
      (node (ref "T9") (pin "E") (pinfunction "E_E") (pintype "passive"))
    )
    (net (code "63") (name "Net-(R22-Pad1)") (class "Default")
      (node (ref "R22") (pin "1") (pinfunction "1_1") (pintype "passive"))
      (node (ref "T10") (pin "E") (pinfunction "E_E") (pintype "passive"))
    )
    (net (code "64") (name "Net-(R25-Pad1)") (class "Default")
      (node (ref "R25") (pin "1") (pinfunction "1_1") (pintype "passive"))
      (node (ref "T11") (pin "E") (pinfunction "E_E") (pintype "passive"))
    )
    (net (code "65") (name "Net-(R26-Pad1)") (class "Default")
      (node (ref "R26") (pin "1") (pinfunction "1_1") (pintype "passive"))
      (node (ref "T12") (pin "E") (pinfunction "E_E") (pintype "passive"))
    )
    (net (code "66") (name "Net-(R40-Pad2)") (class "Default")
      (node (ref "R40") (pin "2") (pinfunction "2_2") (pintype "passive"))
      (node (ref "T18") (pin "E") (pinfunction "E_E") (pintype "passive"))
    )
    (net (code "67") (name "Net-(R43-Pad1)") (class "Default")
      (node (ref "R43") (pin "1") (pinfunction "1_1") (pintype "passive"))
      (node (ref "T13") (pin "E") (pinfunction "E_E") (pintype "passive"))
    )
    (net (code "68") (name "Net-(R44-Pad2)") (class "Default")
      (node (ref "R44") (pin "2") (pinfunction "2_2") (pintype "passive"))
      (node (ref "T14") (pin "E") (pinfunction "E_E") (pintype "passive"))
    )
    (net (code "69") (name "Net-(R46-Pad1)") (class "Default")
      (node (ref "R46") (pin "1") (pinfunction "1_1") (pintype "passive"))
      (node (ref "T17") (pin "E") (pinfunction "E_E") (pintype "passive"))
    )
    (net (code "70") (name "Net-(VGI+-P)") (class "Default")
      (node (ref "R41") (pin "1") (pinfunction "1_1") (pintype "passive"))
      (node (ref "T13") (pin "C") (pinfunction "C_C") (pintype "passive"))
      (node (ref "T17") (pin "C") (pinfunction "C_C") (pintype "passive"))
      (node (ref "VGI+") (pin "1") (pinfunction "P_1") (pintype "passive"))
    )
    (net (code "71") (name "Net-(VGI--P)") (class "Default")
      (node (ref "R42") (pin "2") (pinfunction "2_2") (pintype "passive"))
      (node (ref "T14") (pin "C") (pinfunction "C_C") (pintype "passive"))
      (node (ref "T18") (pin "C") (pinfunction "C_C") (pintype "passive"))
      (node (ref "VGI-") (pin "1") (pinfunction "P_1") (pintype "passive"))
    )
    (net (code "72") (name "Net-(VI+-P)") (class "Default")
      (node (ref "C1") (pin "+") (pinfunction "+_+") (pintype "passive"))
      (node (ref "D5") (pin "C") (pinfunction "C_C") (pintype "passive"))
      (node (ref "Q5") (pin "C") (pinfunction "C_C") (pintype "passive"))
      (node (ref "Q6") (pin "C") (pinfunction "C_C") (pintype "passive"))
      (node (ref "R38") (pin "1") (pinfunction "1_1") (pintype "passive"))
      (node (ref "VI+") (pin "1") (pinfunction "P_1") (pintype "passive"))
    )
    (net (code "73") (name "Net-(VI--P)") (class "Default")
      (node (ref "C1") (pin "-") (pinfunction "-_-") (pintype "passive"))
      (node (ref "C2") (pin "-") (pinfunction "-_-") (pintype "passive"))
      (node (ref "C5") (pin "-") (pinfunction "-_-") (pintype "passive"))
      (node (ref "C6") (pin "-") (pinfunction "-_-") (pintype "passive"))
      (node (ref "R39") (pin "2") (pinfunction "2_2") (pintype "passive"))
      (node (ref "VI-") (pin "1") (pinfunction "P_1") (pintype "passive"))
      (node (ref "VO-") (pin "1") (pinfunction "P_1") (pintype "passive"))
    )
    (net (code "74") (name "Net-(VO+-P)") (class "Default")
      (node (ref "C5") (pin "+") (pinfunction "+_+") (pintype "passive"))
      (node (ref "D5") (pin "A") (pinfunction "A_A") (pintype "passive"))
      (node (ref "Q6") (pin "E") (pinfunction "E_E") (pintype "passive"))
      (node (ref "VO+") (pin "1") (pinfunction "P_1") (pintype "passive"))
    )
    (net (code "75") (name "unconnected-(IC1-Pad2)") (class "Default")
      (node (ref "IC1") (pin "2") (pinfunction "2_2") (pintype "passive"))
    )
    (net (code "76") (name "unconnected-(IC1-Pad6)") (class "Default")
      (node (ref "IC1") (pin "6") (pinfunction "6_6") (pintype "passive"))
    )
    (net (code "77") (name "unconnected-(IC2-Pad2)") (class "Default")
      (node (ref "IC2") (pin "2") (pinfunction "2_2") (pintype "passive"))
    )
    (net (code "78") (name "unconnected-(IC2-Pad6)") (class "Default")
      (node (ref "IC2") (pin "6") (pinfunction "6_6") (pintype "passive"))
    )
    (net (code "79") (name "unconnected-(IC3-Pad2)") (class "Default")
      (node (ref "IC3") (pin "2") (pinfunction "2_2") (pintype "passive"))
    )
    (net (code "80") (name "unconnected-(IC3-Pad6)") (class "Default")
      (node (ref "IC3") (pin "6") (pinfunction "6_6") (pintype "passive"))
    )
    (net (code "81") (name "unconnected-(IC8-Pad2)") (class "Default")
      (node (ref "IC8") (pin "2") (pinfunction "2_2") (pintype "passive"))
    )
    (net (code "82") (name "unconnected-(IC8-Pad6)") (class "Default")
      (node (ref "IC8") (pin "6") (pinfunction "6_6") (pintype "passive"))
    )
    (net (code "83") (name "unconnected-(IC9-Pad2)") (class "Default")
      (node (ref "IC9") (pin "2") (pinfunction "2_2") (pintype "passive"))
    )
    (net (code "84") (name "unconnected-(IC9-Pad6)") (class "Default")
      (node (ref "IC9") (pin "6") (pinfunction "6_6") (pintype "passive"))
    )
    (net (code "85") (name "unconnected-(IC10-Pad2)") (class "Default")
      (node (ref "IC10") (pin "2") (pinfunction "2_2") (pintype "passive"))
    )
    (net (code "86") (name "unconnected-(IC10-Pad6)") (class "Default")
      (node (ref "IC10") (pin "6") (pinfunction "6_6") (pintype "passive"))
    )
    (net (code "87") (name "unconnected-(IC11-Pad2)") (class "Default")
      (node (ref "IC11") (pin "2") (pinfunction "2_2") (pintype "passive"))
    )
    (net (code "88") (name "unconnected-(IC11-Pad6)") (class "Default")
      (node (ref "IC11") (pin "6") (pinfunction "6_6") (pintype "passive"))
    )
    (net (code "89") (name "unconnected-(IC12-Pad2)") (class "Default")
      (node (ref "IC12") (pin "2") (pinfunction "2_2") (pintype "passive"))
    )
    (net (code "90") (name "unconnected-(IC12-Pad6)") (class "Default")
      (node (ref "IC12") (pin "6") (pinfunction "6_6") (pintype "passive"))
    )
  )
)
